# SCH_NFC-card-Rhyah-Singh_2024-10-10.net
KiCad netlist of a schematic drawn in EasyEDA
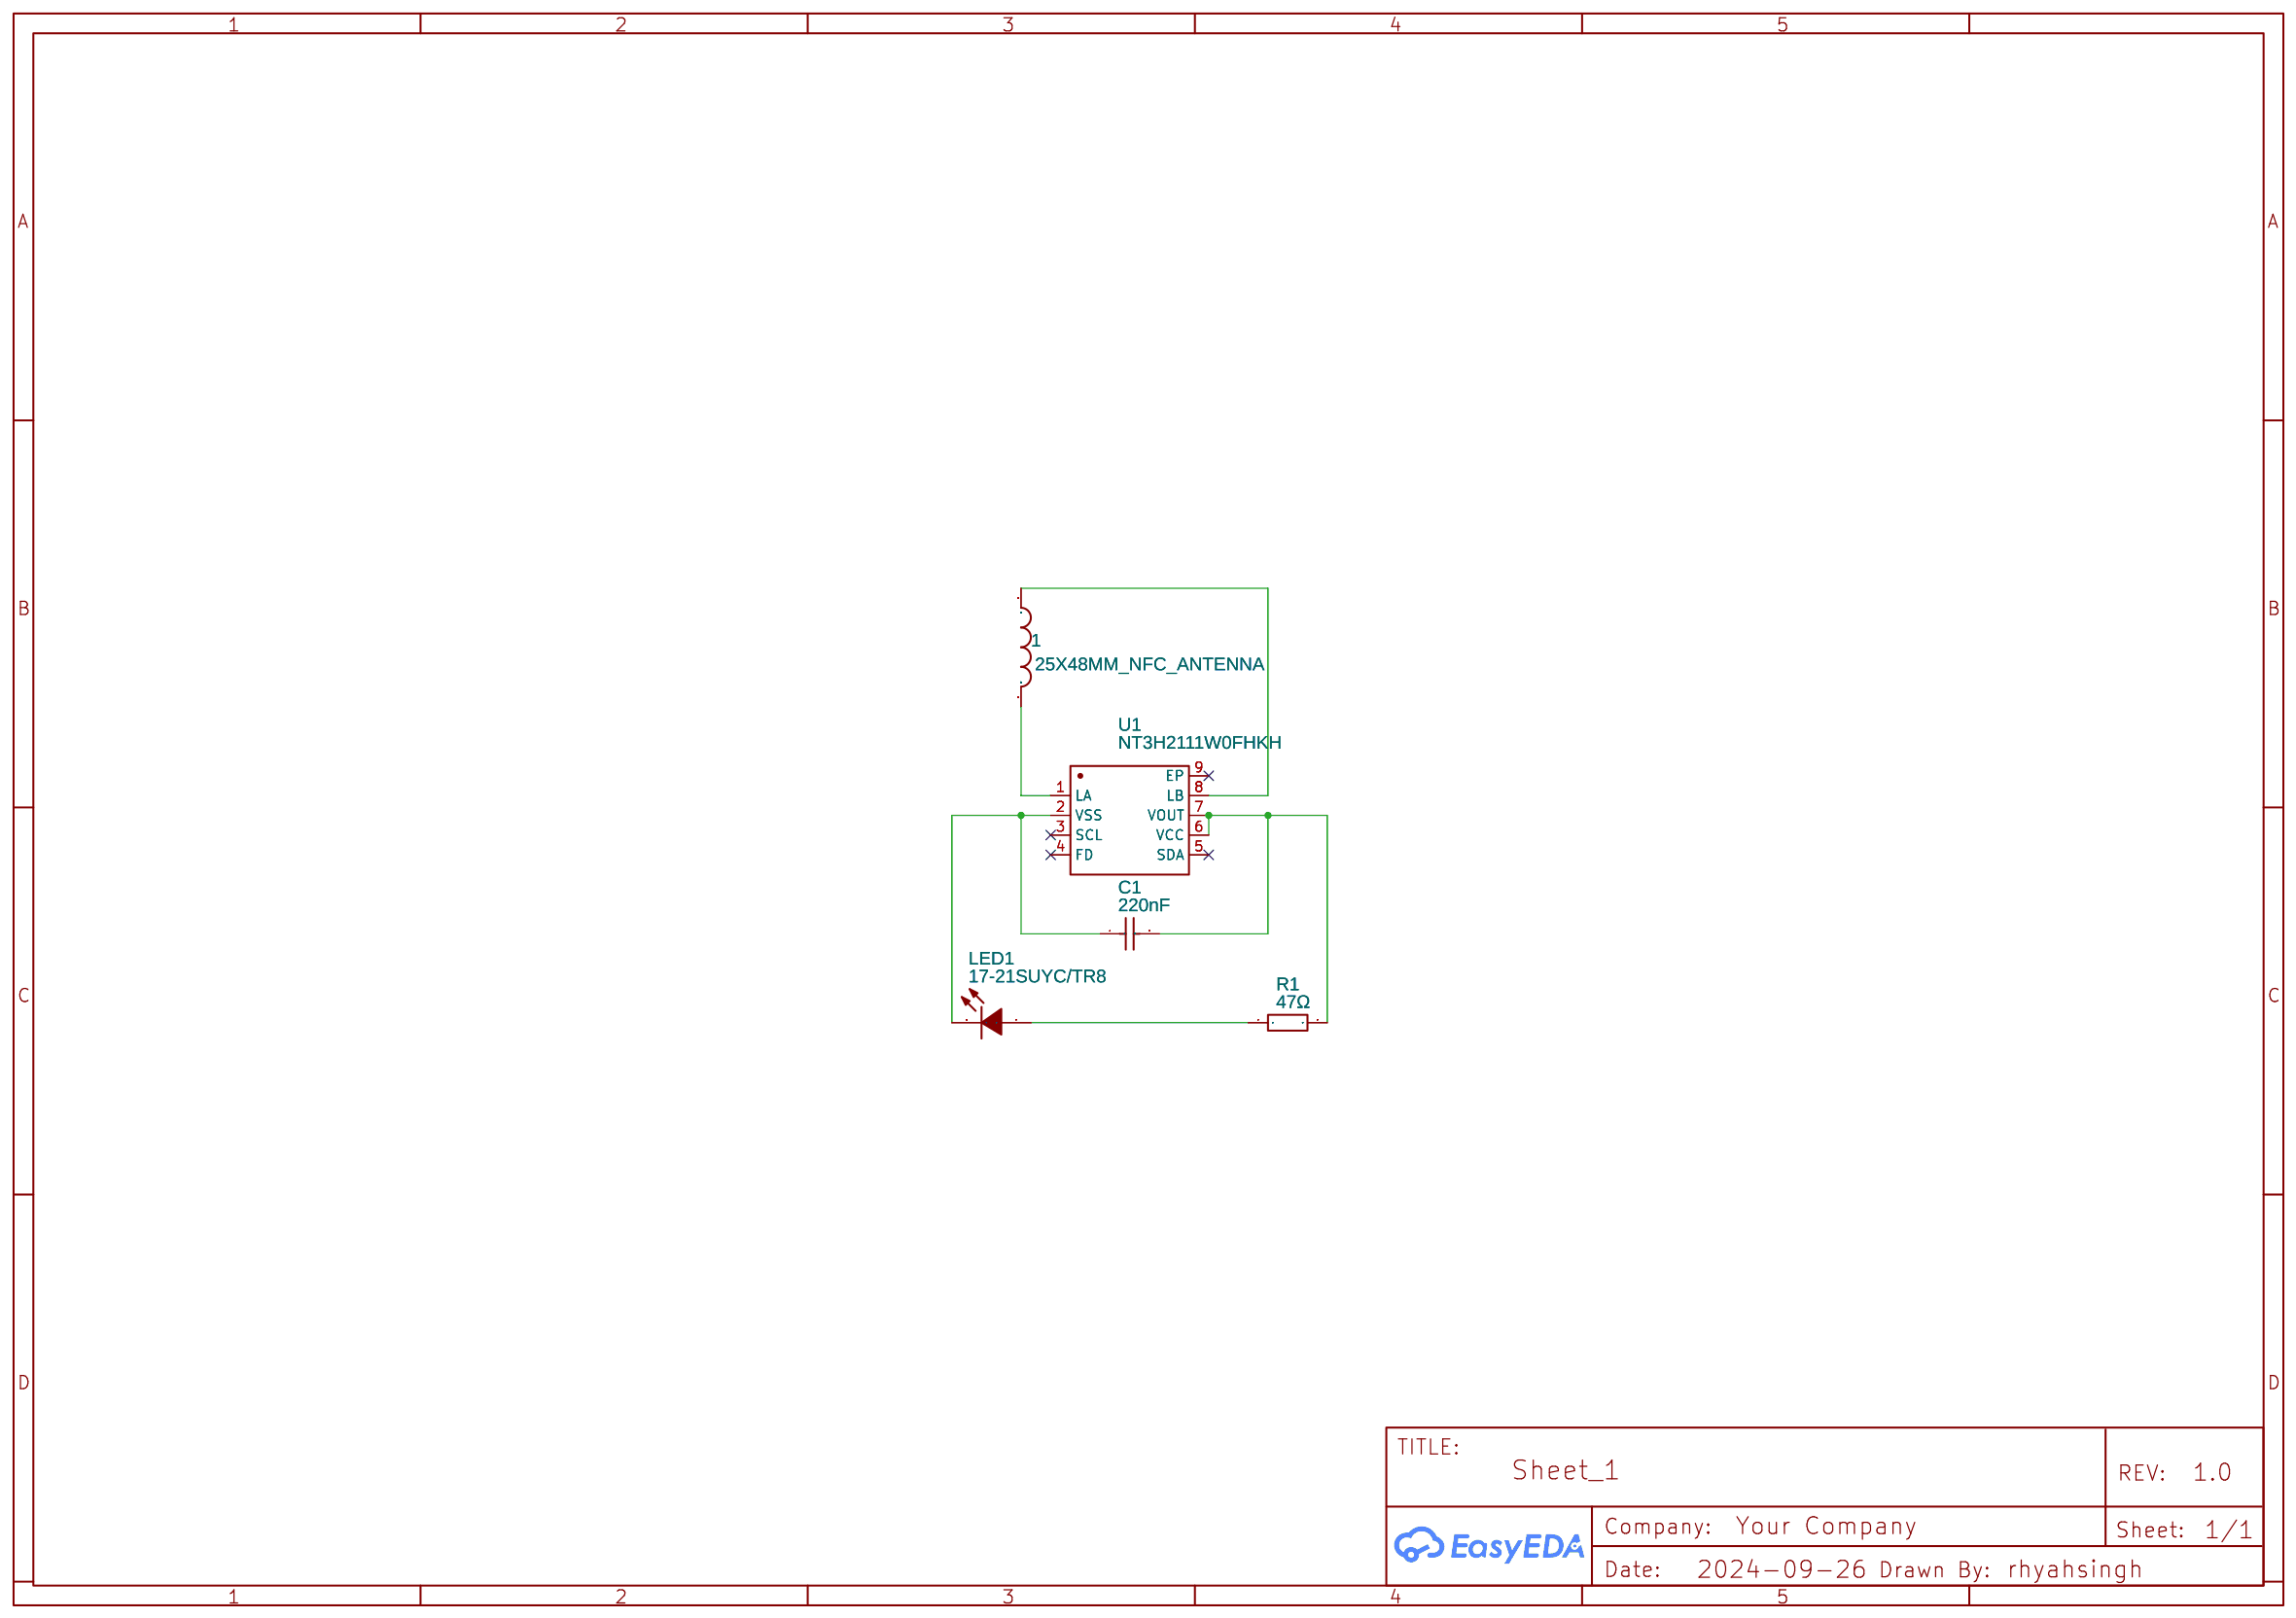
[diagram p0: schematic sheet]

(export (version "E")
  (design (tool "Eeschema 10.0.6"))
  (components
    (comp (ref "1") (value "25X48MM_NFC_ANTENNA") (libsource (lib "") (part "25X48MM_NFC_ANTENNA")))
    (comp (ref "C1")
      (value "220nF")
      (fields
        (field (name "Manufacturer Part") "CL10B224KA8NNNC")
        (field (name "Manufacturer") "SAMSUNG(三星)")
      )
      (libsource (lib "") (part "CL10B224KA8NNNC"))
    )
    (comp (ref "LED1")
      (value "17-21SUYC/TR8")
      (fields (field (name "Manufacturer Part") "KT-0805黄灯") (field (name "Manufacturer") "KENTO"))
      (libsource (lib "") (part "17-21SUYC/TR8"))
    )
    (comp (ref "R1")
      (value "47Ω")
      (fields
        (field (name "Manufacturer Part") "0603WAF470JT5E")
        (field (name "Manufacturer") "UNI-ROYAL(厚声)")
      )
      (libsource (lib "") (part "0603WAF470JT5E"))
    )
    (comp (ref "U1")
      (value "NT3H2111W0FHKH")
      (fields (field (name "Manufacturer") "NXP(恩智浦)"))
      (libsource (lib "") (part "NT3H2111W0FHKH"))
    )
  )
  (nets
    (net (code "1") (name "Net-(LED1-+)") (class "Default")
      (node (ref "LED1") (pin "1") (pinfunction "+_1") (pintype "unspecified"))
      (node (ref "R1") (pin "1") (pinfunction "1_1") (pintype "input"))
    )
    (net (code "2") (name "Net-(LED1--)") (class "Default")
      (node (ref "C1") (pin "1") (pinfunction "1_1") (pintype "input"))
      (node (ref "LED1") (pin "2") (pinfunction "-_2") (pintype "unspecified"))
      (node (ref "U1") (pin "2") (pinfunction "VSS_2") (pintype "unspecified"))
    )
    (net (code "3") (name "Net-(U1-LA)") (class "Default")
      (node (ref "1") (pin "P$2") (pinfunction "P$2_P$2") (pintype "bidirectional"))
      (node (ref "U1") (pin "1") (pinfunction "LA_1") (pintype "unspecified"))
    )
    (net (code "4") (name "Net-(U1-LB)") (class "Default")
      (node (ref "1") (pin "P$1") (pinfunction "P$1_P$1") (pintype "bidirectional"))
      (node (ref "U1") (pin "8") (pinfunction "LB_8") (pintype "unspecified"))
    )
    (net (code "5") (name "Net-(U1-VCC)") (class "Default")
      (node (ref "C1") (pin "2") (pinfunction "2_2") (pintype "input"))
      (node (ref "R1") (pin "2") (pinfunction "2_2") (pintype "input"))
      (node (ref "U1") (pin "6") (pinfunction "VCC_6") (pintype "unspecified"))
      (node (ref "U1") (pin "7") (pinfunction "VOUT_7") (pintype "unspecified"))
    )
    (net (code "6") (name "unconnected-(U1-EP-Pad9)") (class "Default")
      (node (ref "U1") (pin "9") (pinfunction "EP_9") (pintype "unspecified+no_connect"))
    )
    (net (code "7") (name "unconnected-(U1-FD-Pad4)") (class "Default")
      (node (ref "U1") (pin "4") (pinfunction "FD_4") (pintype "unspecified+no_connect"))
    )
    (net (code "8") (name "unconnected-(U1-SCL-Pad3)") (class "Default")
      (node (ref "U1") (pin "3") (pinfunction "SCL_3") (pintype "unspecified+no_connect"))
    )
    (net (code "9") (name "unconnected-(U1-SDA-Pad5)") (class "Default")
      (node (ref "U1") (pin "5") (pinfunction "SDA_5") (pintype "unspecified+no_connect"))
    )
  )
)
